# Button_Led.net
KiCad netlist of a schematic drawn in EAGLE
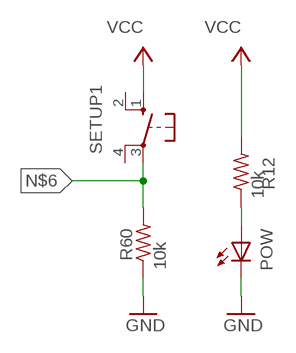
[diagram p0: schematic, sheet 1]

(export (version "E")
  (design (tool "Eeschema 10.0.6"))
  (components
    (comp (ref "POW")
      (value "LED3MM")
      (footprint "eagle-import:LED3MM")
      (libsource (lib "eagle-import") (part "LED3MM"))
    )
    (comp (ref "R12")
      (value "10k")
      (footprint "eagle-import:R0805")
      (libsource (lib "eagle-import") (part "R-US_R0805"))
    )
    (comp (ref "R60")
      (value "10k")
      (footprint "eagle-import:R0805")
      (libsource (lib "eagle-import") (part "R-US_R0805"))
    )
    (comp (ref "SETUP1")
      (value "10-XX")
      (footprint "eagle-import:B3F-10XX")
      (fields (field (name "MPN") "B3F-1000"))
      (libsource (lib "eagle-import") (part "10-XX"))
    )
  )
  (nets
    (net (code "1") (name "GND") (class "Default")
      (node (ref "POW") (pin "K") (pinfunction "C_K") (pintype "passive"))
      (node (ref "R60") (pin "1") (pinfunction "1_1") (pintype "passive"))
    )
    (net (code "2") (name "N$6") (class "Default")
      (node (ref "R60") (pin "2") (pinfunction "2_2") (pintype "passive"))
      (node (ref "SETUP1") (pin "3") (pinfunction "P_3") (pintype "passive"))
    )
    (net (code "3") (name "Net-(POW-PadA)") (class "Default")
      (node (ref "POW") (pin "A") (pinfunction "A_A") (pintype "passive"))
      (node (ref "R12") (pin "1") (pinfunction "1_1") (pintype "passive"))
    )
    (net (code "4") (name "VCC") (class "Default")
      (node (ref "R12") (pin "2") (pinfunction "2_2") (pintype "passive"))
      (node (ref "SETUP1") (pin "1") (pinfunction "S_1") (pintype "passive"))
    )
    (net (code "5") (name "unconnected-(SETUP1-P1-Pad4)") (class "Default")
      (node (ref "SETUP1") (pin "4") (pinfunction "P1_4") (pintype "passive"))
    )
    (net (code "6") (name "unconnected-(SETUP1-S1-Pad2)") (class "Default")
      (node (ref "SETUP1") (pin "2") (pinfunction "S1_2") (pintype "passive"))
    )
  )
)
